# Robot_Board_v003.net
KiCad netlist of a schematic drawn in EAGLE
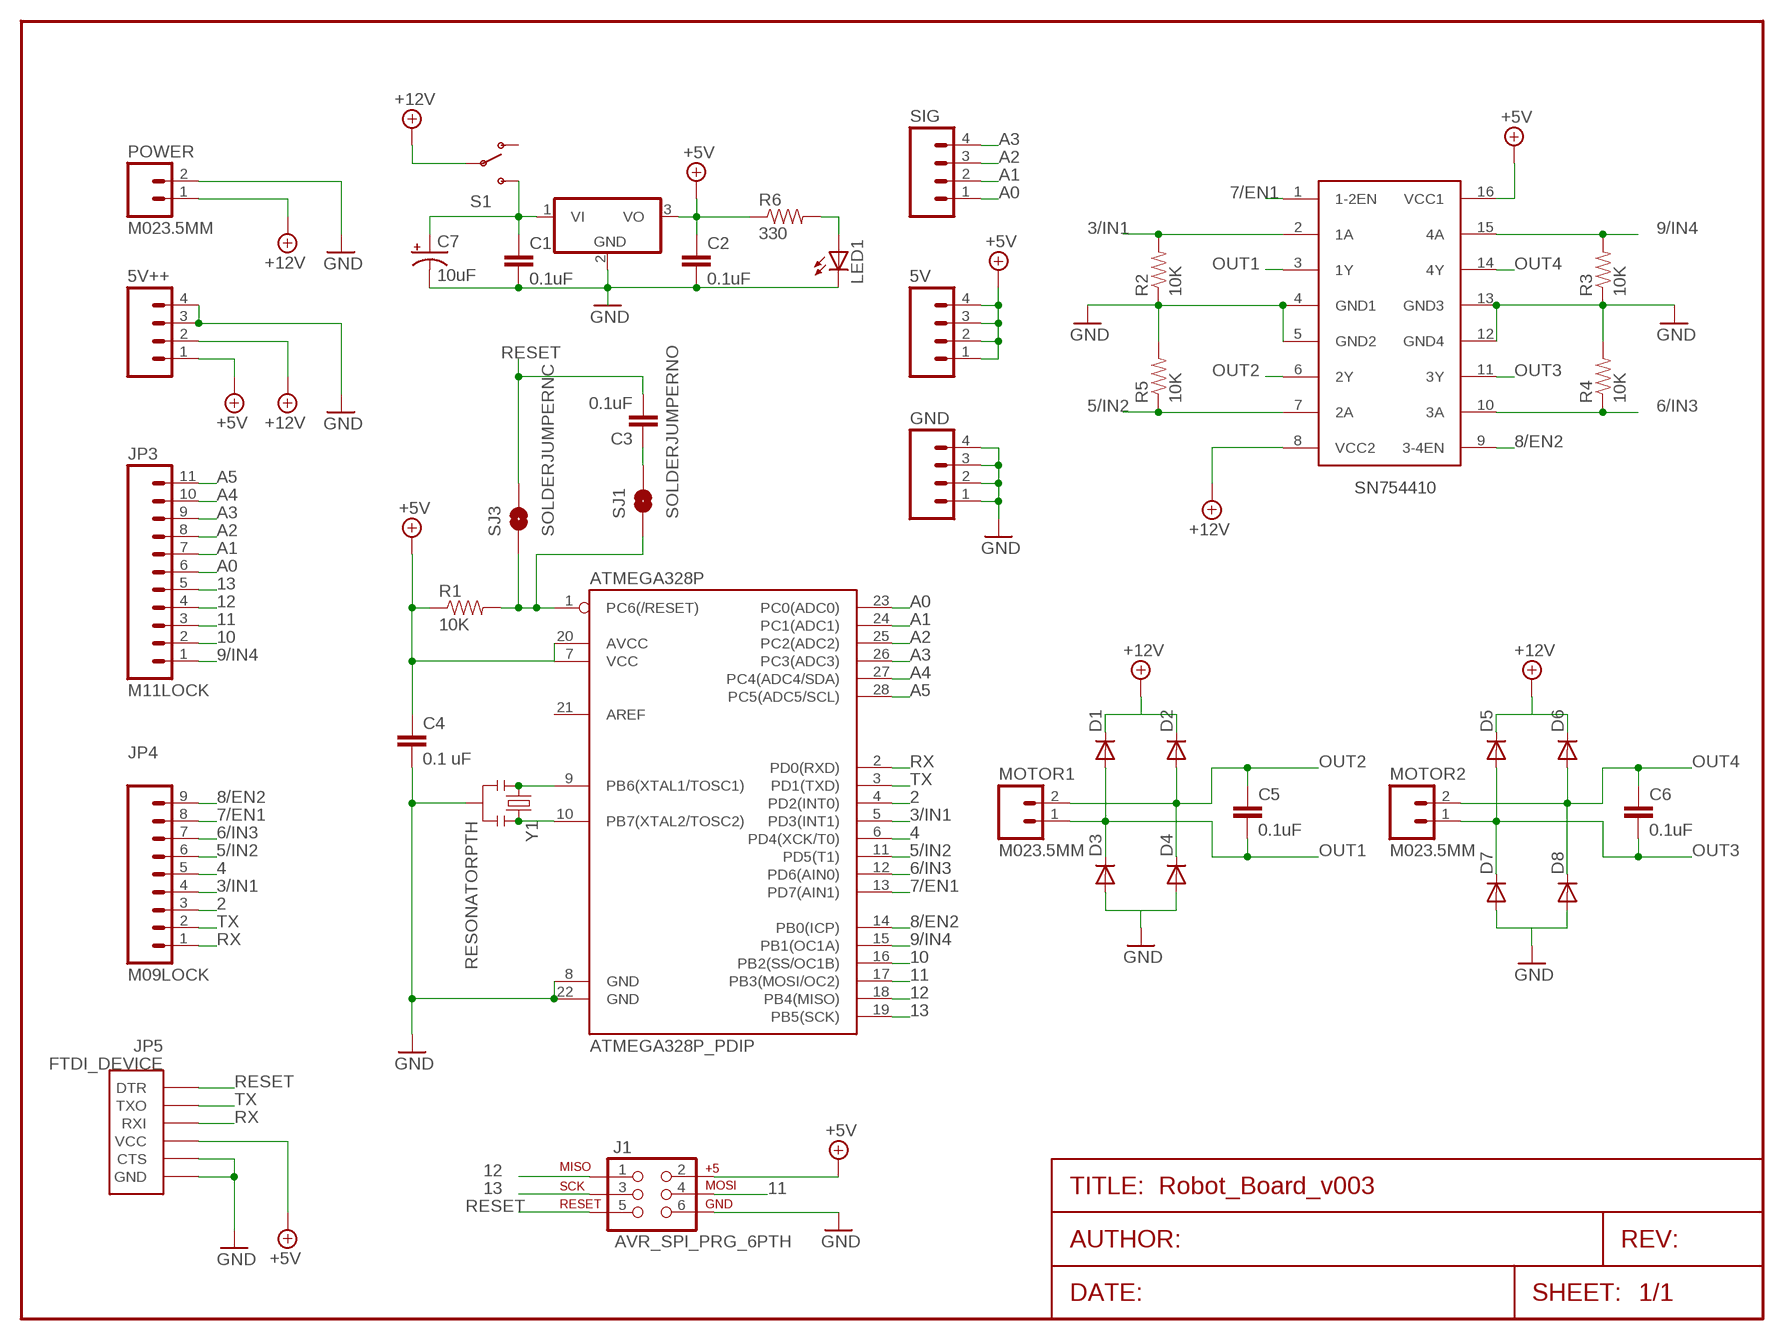
[diagram p0: schematic, sheet 1]

(export (version "E")
  (design (tool "Eeschema 10.0.6"))
  (components
    (comp (ref "5V")
      (value "M04PTH")
      (footprint "eagle-import:1X04")
      (libsource (lib "eagle-import") (part "M04PTH"))
    )
    (comp (ref "5V++")
      (value "M04LOCK")
      (footprint "eagle-import:1X04_LOCK")
      (libsource (lib "eagle-import") (part "M04LOCK"))
    )
    (comp (ref "7805")
      (value "7805TV")
      (footprint "eagle-import:TO220V")
      (libsource (lib "eagle-import") (part "78TV05"))
    )
    (comp (ref "ATMEGA328P")
      (value "ATMEGA328P_PDIP")
      (footprint "eagle-import:DIL28-3")
      (libsource (lib "eagle-import") (part "ATMEGA328P_PDIP"))
    )
    (comp (ref "C1")
      (value "0.1uF")
      (footprint "eagle-import:CAP-PTH-5MM")
      (libsource (lib "eagle-import") (part "CAPPTH1"))
    )
    (comp (ref "C2")
      (value "0.1uF")
      (footprint "eagle-import:CAP-PTH-5MM")
      (libsource (lib "eagle-import") (part "CAPPTH1"))
    )
    (comp (ref "C3")
      (value "0.1uF")
      (footprint "eagle-import:CAP-PTH-5MM")
      (libsource (lib "eagle-import") (part "CAPPTH1"))
    )
    (comp (ref "C4")
      (value "0.1 uF")
      (footprint "eagle-import:CAP-PTH-5MM")
      (libsource (lib "eagle-import") (part "CAPPTH1"))
    )
    (comp (ref "C5")
      (value "0.1uF")
      (footprint "eagle-import:CAP-PTH-5MM")
      (libsource (lib "eagle-import") (part "CAPPTH1"))
    )
    (comp (ref "C6")
      (value "0.1uF")
      (footprint "eagle-import:CAP-PTH-5MM")
      (libsource (lib "eagle-import") (part "CAPPTH1"))
    )
    (comp (ref "C7")
      (value "10uF")
      (footprint "eagle-import:CPOL-RADIAL-10UF-25V")
      (libsource (lib "eagle-import") (part "CAP_POLPTH2"))
    )
    (comp (ref "D1")
      (value "DIODEPTH")
      (footprint "eagle-import:DIODE-1N4001")
      (libsource (lib "eagle-import") (part "DIODEPTH"))
    )
    (comp (ref "D2")
      (value "DIODEPTH")
      (footprint "eagle-import:DIODE-1N4001")
      (libsource (lib "eagle-import") (part "DIODEPTH"))
    )
    (comp (ref "D3")
      (value "DIODEPTH")
      (footprint "eagle-import:DIODE-1N4001")
      (libsource (lib "eagle-import") (part "DIODEPTH"))
    )
    (comp (ref "D4")
      (value "DIODEPTH")
      (footprint "eagle-import:DIODE-1N4001")
      (libsource (lib "eagle-import") (part "DIODEPTH"))
    )
    (comp (ref "D5")
      (value "DIODEPTH")
      (footprint "eagle-import:DIODE-1N4001")
      (libsource (lib "eagle-import") (part "DIODEPTH"))
    )
    (comp (ref "D6")
      (value "DIODEPTH")
      (footprint "eagle-import:DIODE-1N4001")
      (libsource (lib "eagle-import") (part "DIODEPTH"))
    )
    (comp (ref "D7")
      (value "DIODEPTH")
      (footprint "eagle-import:DIODE-1N4001")
      (libsource (lib "eagle-import") (part "DIODEPTH"))
    )
    (comp (ref "D8")
      (value "DIODEPTH")
      (footprint "eagle-import:DIODE-1N4001")
      (libsource (lib "eagle-import") (part "DIODEPTH"))
    )
    (comp (ref "GND")
      (value "M04PTH")
      (footprint "eagle-import:1X04")
      (libsource (lib "eagle-import") (part "M04PTH"))
    )
    (comp (ref "J1")
      (value "AVR_SPI_PRG_6PTH")
      (footprint "eagle-import:2X3")
      (libsource (lib "eagle-import") (part "AVR_SPI_PRG_6PTH"))
    )
    (comp (ref "JP3")
      (value "M11LOCK")
      (footprint "eagle-import:1X11_LOCK")
      (libsource (lib "eagle-import") (part "M11LOCK"))
    )
    (comp (ref "JP4")
      (value "M09LOCK")
      (footprint "eagle-import:1X09_LOCK")
      (libsource (lib "eagle-import") (part "M09LOCK"))
    )
    (comp (ref "JP5")
      (value "FTDI_DEVICE")
      (footprint "eagle-import:FTDI_DEVICE_SIDE")
      (libsource (lib "eagle-import") (part "FTDI_DEVICE"))
    )
    (comp (ref "LED1")
      (value "LED3MM")
      (footprint "eagle-import:LED3MM")
      (libsource (lib "eagle-import") (part "LED3MM"))
    )
    (comp (ref "MOTOR1")
      (value "M023.5MM")
      (footprint "eagle-import:SCREWTERMINAL-3.5MM-2")
      (libsource (lib "eagle-import") (part "M023.5MM"))
    )
    (comp (ref "MOTOR2")
      (value "M023.5MM")
      (footprint "eagle-import:SCREWTERMINAL-3.5MM-2")
      (libsource (lib "eagle-import") (part "M023.5MM"))
    )
    (comp (ref "POWER")
      (value "M023.5MM")
      (footprint "eagle-import:SCREWTERMINAL-3.5MM-2")
      (libsource (lib "eagle-import") (part "M023.5MM"))
    )
    (comp (ref "R1")
      (value "10K")
      (footprint "eagle-import:AXIAL-0.4")
      (libsource (lib "eagle-import") (part "RESISTORPTH-1/4W"))
    )
    (comp (ref "R2")
      (value "10K")
      (footprint "eagle-import:AXIAL-0.4")
      (libsource (lib "eagle-import") (part "RESISTORPTH-1/4W"))
    )
    (comp (ref "R3")
      (value "10K")
      (footprint "eagle-import:AXIAL-0.4")
      (libsource (lib "eagle-import") (part "RESISTORPTH-1/4W"))
    )
    (comp (ref "R4")
      (value "10K")
      (footprint "eagle-import:AXIAL-0.4")
      (libsource (lib "eagle-import") (part "RESISTORPTH-1/4W"))
    )
    (comp (ref "R5")
      (value "10K")
      (footprint "eagle-import:AXIAL-0.4")
      (libsource (lib "eagle-import") (part "RESISTORPTH-1/4W"))
    )
    (comp (ref "R6")
      (value "330")
      (footprint "eagle-import:AXIAL-0.4")
      (libsource (lib "eagle-import") (part "RESISTORPTH-1/4W"))
    )
    (comp (ref "S1")
      (value "SWITCH-SPDTPTH")
      (footprint "eagle-import:SWITCH-SPDT")
      (libsource (lib "eagle-import") (part "SWITCH-SPDTPTH"))
    )
    (comp (ref "SIG")
      (value "M04PTH")
      (footprint "eagle-import:1X04")
      (libsource (lib "eagle-import") (part "M04PTH"))
    )
    (comp (ref "SJ1")
      (value "SOLDERJUMPERNO")
      (footprint "eagle-import:SJ_2S-NO")
      (libsource (lib "eagle-import") (part "SOLDERJUMPERNO"))
    )
    (comp (ref "SJ3")
      (value "SOLDERJUMPERNC")
      (footprint "eagle-import:SJ_2S")
      (libsource (lib "eagle-import") (part "SOLDERJUMPERNC"))
    )
    (comp (ref "SN754410")
      (value "L293D")
      (footprint "eagle-import:DIL16")
      (libsource (lib "eagle-import") (part "L293D"))
    )
    (comp (ref "Y1")
      (value "RESONATORPTH")
      (footprint "eagle-import:RESONATOR-PTH")
      (libsource (lib "eagle-import") (part "RESONATORPTH"))
    )
  )
  (nets
    (net (code "1") (name "+5V") (class "Default")
      (node (ref "5V") (pin "1") (pinfunction "1_1") (pintype "passive"))
      (node (ref "5V") (pin "2") (pinfunction "2_2") (pintype "passive"))
      (node (ref "5V") (pin "3") (pinfunction "3_3") (pintype "passive"))
      (node (ref "5V") (pin "4") (pinfunction "4_4") (pintype "passive"))
      (node (ref "5V++") (pin "1") (pinfunction "1_1") (pintype "passive"))
      (node (ref "7805") (pin "3") (pinfunction "VO_3") (pintype "passive"))
      (node (ref "ATMEGA328P") (pin "20") (pinfunction "AVCC_20") (pintype "bidirectional"))
      (node (ref "ATMEGA328P") (pin "7") (pinfunction "VCC_7") (pintype "bidirectional"))
      (node (ref "C2") (pin "1") (pinfunction "1_1") (pintype "passive"))
      (node (ref "C4") (pin "1") (pinfunction "1_1") (pintype "passive"))
      (node (ref "J1") (pin "2") (pinfunction "2_2") (pintype "passive"))
      (node (ref "JP5") (pin "P$4") (pinfunction "VCC_P$4") (pintype "bidirectional"))
      (node (ref "R1") (pin "P$1") (pinfunction "1_P$1") (pintype "passive"))
      (node (ref "R6") (pin "P$1") (pinfunction "1_P$1") (pintype "passive"))
      (node (ref "SN754410") (pin "16") (pinfunction "VCC1_16") (pintype "power_in"))
    )
    (net (code "2") (name "+12V") (class "Default")
      (node (ref "5V++") (pin "2") (pinfunction "2_2") (pintype "passive"))
      (node (ref "D1") (pin "C") (pinfunction "C_C") (pintype "passive"))
      (node (ref "D2") (pin "C") (pinfunction "C_C") (pintype "passive"))
      (node (ref "D5") (pin "C") (pinfunction "C_C") (pintype "passive"))
      (node (ref "D6") (pin "C") (pinfunction "C_C") (pintype "passive"))
      (node (ref "POWER") (pin "1") (pinfunction "1_1") (pintype "passive"))
      (node (ref "S1") (pin "2") (pinfunction "P_2") (pintype "passive"))
      (node (ref "SN754410") (pin "8") (pinfunction "VCC2_8") (pintype "power_in"))
    )
    (net (code "3") (name "/2") (class "Default")
      (node (ref "ATMEGA328P") (pin "4") (pinfunction "PD2(INT0)_4") (pintype "bidirectional"))
      (node (ref "JP4") (pin "3") (pinfunction "3_3") (pintype "passive"))
    )
    (net (code "4") (name "/3{slash}IN1") (class "Default")
      (node (ref "ATMEGA328P") (pin "5") (pinfunction "PD3(INT1)_5") (pintype "bidirectional"))
      (node (ref "JP4") (pin "4") (pinfunction "4_4") (pintype "passive"))
      (node (ref "R2") (pin "P$2") (pinfunction "2_P$2") (pintype "passive"))
      (node (ref "SN754410") (pin "2") (pinfunction "1A_2") (pintype "input"))
    )
    (net (code "5") (name "/4") (class "Default")
      (node (ref "ATMEGA328P") (pin "6") (pinfunction "PD4(XCK/T0)_6") (pintype "bidirectional"))
      (node (ref "JP4") (pin "5") (pinfunction "5_5") (pintype "passive"))
    )
    (net (code "6") (name "/5{slash}IN2") (class "Default")
      (node (ref "ATMEGA328P") (pin "11") (pinfunction "PD5(T1)_11") (pintype "bidirectional"))
      (node (ref "JP4") (pin "6") (pinfunction "6_6") (pintype "passive"))
      (node (ref "R5") (pin "P$1") (pinfunction "1_P$1") (pintype "passive"))
      (node (ref "SN754410") (pin "7") (pinfunction "2A_7") (pintype "input"))
    )
    (net (code "7") (name "/6{slash}IN3") (class "Default")
      (node (ref "ATMEGA328P") (pin "12") (pinfunction "PD6(AIN0)_12") (pintype "bidirectional"))
      (node (ref "JP4") (pin "7") (pinfunction "7_7") (pintype "passive"))
      (node (ref "R4") (pin "P$1") (pinfunction "1_P$1") (pintype "passive"))
      (node (ref "SN754410") (pin "10") (pinfunction "3A_10") (pintype "input"))
    )
    (net (code "8") (name "/7{slash}EN1") (class "Default")
      (node (ref "ATMEGA328P") (pin "13") (pinfunction "PD7(AIN1)_13") (pintype "bidirectional"))
      (node (ref "JP4") (pin "8") (pinfunction "8_8") (pintype "passive"))
      (node (ref "SN754410") (pin "1") (pinfunction "1-2EN_1") (pintype "input"))
    )
    (net (code "9") (name "/8{slash}EN2") (class "Default")
      (node (ref "ATMEGA328P") (pin "14") (pinfunction "PB0(ICP)_14") (pintype "bidirectional"))
      (node (ref "JP4") (pin "9") (pinfunction "9_9") (pintype "passive"))
      (node (ref "SN754410") (pin "9") (pinfunction "3-4EN_9") (pintype "input"))
    )
    (net (code "10") (name "/9{slash}IN4") (class "Default")
      (node (ref "ATMEGA328P") (pin "15") (pinfunction "PB1(OC1A)_15") (pintype "bidirectional"))
      (node (ref "JP3") (pin "1") (pinfunction "1_1") (pintype "passive"))
      (node (ref "R3") (pin "P$2") (pinfunction "2_P$2") (pintype "passive"))
      (node (ref "SN754410") (pin "15") (pinfunction "4A_15") (pintype "input"))
    )
    (net (code "11") (name "/10") (class "Default")
      (node (ref "ATMEGA328P") (pin "16") (pinfunction "PB2(SS/OC1B)_16") (pintype "bidirectional"))
      (node (ref "JP3") (pin "2") (pinfunction "2_2") (pintype "passive"))
    )
    (net (code "12") (name "/11") (class "Default")
      (node (ref "ATMEGA328P") (pin "17") (pinfunction "PB3(MOSI/OC2)_17") (pintype "bidirectional"))
      (node (ref "J1") (pin "4") (pinfunction "4_4") (pintype "passive"))
      (node (ref "JP3") (pin "3") (pinfunction "3_3") (pintype "passive"))
    )
    (net (code "13") (name "/12") (class "Default")
      (node (ref "ATMEGA328P") (pin "18") (pinfunction "PB4(MISO)_18") (pintype "bidirectional"))
      (node (ref "J1") (pin "1") (pinfunction "1_1") (pintype "passive"))
      (node (ref "JP3") (pin "4") (pinfunction "4_4") (pintype "passive"))
    )
    (net (code "14") (name "/13") (class "Default")
      (node (ref "ATMEGA328P") (pin "19") (pinfunction "PB5(SCK)_19") (pintype "bidirectional"))
      (node (ref "J1") (pin "3") (pinfunction "3_3") (pintype "passive"))
      (node (ref "JP3") (pin "5") (pinfunction "5_5") (pintype "passive"))
    )
    (net (code "15") (name "/A0") (class "Default")
      (node (ref "ATMEGA328P") (pin "23") (pinfunction "PC0(ADC0)_23") (pintype "bidirectional"))
      (node (ref "JP3") (pin "6") (pinfunction "6_6") (pintype "passive"))
      (node (ref "SIG") (pin "1") (pinfunction "1_1") (pintype "passive"))
    )
    (net (code "16") (name "/A1") (class "Default")
      (node (ref "ATMEGA328P") (pin "24") (pinfunction "PC1(ADC1)_24") (pintype "bidirectional"))
      (node (ref "JP3") (pin "7") (pinfunction "7_7") (pintype "passive"))
      (node (ref "SIG") (pin "2") (pinfunction "2_2") (pintype "passive"))
    )
    (net (code "17") (name "/A2") (class "Default")
      (node (ref "ATMEGA328P") (pin "25") (pinfunction "PC2(ADC2)_25") (pintype "bidirectional"))
      (node (ref "JP3") (pin "8") (pinfunction "8_8") (pintype "passive"))
      (node (ref "SIG") (pin "3") (pinfunction "3_3") (pintype "passive"))
    )
    (net (code "18") (name "/A3") (class "Default")
      (node (ref "ATMEGA328P") (pin "26") (pinfunction "PC3(ADC3)_26") (pintype "bidirectional"))
      (node (ref "JP3") (pin "9") (pinfunction "9_9") (pintype "passive"))
      (node (ref "SIG") (pin "4") (pinfunction "4_4") (pintype "passive"))
    )
    (net (code "19") (name "/A4") (class "Default")
      (node (ref "ATMEGA328P") (pin "27") (pinfunction "PC4(ADC4/SDA)_27") (pintype "bidirectional"))
      (node (ref "JP3") (pin "10") (pinfunction "10_10") (pintype "passive"))
    )
    (net (code "20") (name "/A5") (class "Default")
      (node (ref "ATMEGA328P") (pin "28") (pinfunction "PC5(ADC5/SCL)_28") (pintype "bidirectional"))
      (node (ref "JP3") (pin "11") (pinfunction "11_11") (pintype "passive"))
    )
    (net (code "21") (name "/OUT1") (class "Default")
      (node (ref "C5") (pin "2") (pinfunction "2_2") (pintype "passive"))
      (node (ref "D1") (pin "A") (pinfunction "A_A") (pintype "passive"))
      (node (ref "D3") (pin "C") (pinfunction "C_C") (pintype "passive"))
      (node (ref "MOTOR1") (pin "1") (pinfunction "1_1") (pintype "passive"))
      (node (ref "SN754410") (pin "3") (pinfunction "1Y_3") (pintype "output"))
    )
    (net (code "22") (name "/OUT2") (class "Default")
      (node (ref "C5") (pin "1") (pinfunction "1_1") (pintype "passive"))
      (node (ref "D2") (pin "A") (pinfunction "A_A") (pintype "passive"))
      (node (ref "D4") (pin "C") (pinfunction "C_C") (pintype "passive"))
      (node (ref "MOTOR1") (pin "2") (pinfunction "2_2") (pintype "passive"))
      (node (ref "SN754410") (pin "6") (pinfunction "2Y_6") (pintype "output"))
    )
    (net (code "23") (name "/OUT3") (class "Default")
      (node (ref "C6") (pin "2") (pinfunction "2_2") (pintype "passive"))
      (node (ref "D5") (pin "A") (pinfunction "A_A") (pintype "passive"))
      (node (ref "D7") (pin "C") (pinfunction "C_C") (pintype "passive"))
      (node (ref "MOTOR2") (pin "1") (pinfunction "1_1") (pintype "passive"))
      (node (ref "SN754410") (pin "11") (pinfunction "3Y_11") (pintype "output"))
    )
    (net (code "24") (name "/OUT4") (class "Default")
      (node (ref "C6") (pin "1") (pinfunction "1_1") (pintype "passive"))
      (node (ref "D6") (pin "A") (pinfunction "A_A") (pintype "passive"))
      (node (ref "D8") (pin "C") (pinfunction "C_C") (pintype "passive"))
      (node (ref "MOTOR2") (pin "2") (pinfunction "2_2") (pintype "passive"))
      (node (ref "SN754410") (pin "14") (pinfunction "4Y_14") (pintype "output"))
    )
    (net (code "25") (name "/RESET") (class "Default")
      (node (ref "C3") (pin "2") (pinfunction "2_2") (pintype "passive"))
      (node (ref "J1") (pin "5") (pinfunction "5_5") (pintype "passive"))
      (node (ref "JP5") (pin "P$1") (pinfunction "DTR_P$1") (pintype "bidirectional"))
      (node (ref "SJ3") (pin "2") (pinfunction "2_2") (pintype "passive"))
    )
    (net (code "26") (name "/RX") (class "Default")
      (node (ref "ATMEGA328P") (pin "2") (pinfunction "PD0(RXD)_2") (pintype "bidirectional"))
      (node (ref "JP4") (pin "1") (pinfunction "1_1") (pintype "passive"))
      (node (ref "JP5") (pin "P$3") (pinfunction "RXI_P$3") (pintype "bidirectional"))
    )
    (net (code "27") (name "/TX") (class "Default")
      (node (ref "ATMEGA328P") (pin "3") (pinfunction "PD1(TXD)_3") (pintype "bidirectional"))
      (node (ref "JP4") (pin "2") (pinfunction "2_2") (pintype "passive"))
      (node (ref "JP5") (pin "P$2") (pinfunction "TXO_P$2") (pintype "bidirectional"))
    )
    (net (code "28") (name "GND") (class "Default")
      (node (ref "5V++") (pin "3") (pinfunction "3_3") (pintype "passive"))
      (node (ref "5V++") (pin "4") (pinfunction "4_4") (pintype "passive"))
      (node (ref "7805") (pin "2") (pinfunction "GND_2") (pintype "passive"))
      (node (ref "ATMEGA328P") (pin "22") (pinfunction "GND_22") (pintype "bidirectional"))
      (node (ref "ATMEGA328P") (pin "8") (pinfunction "GND_8") (pintype "bidirectional"))
      (node (ref "C1") (pin "2") (pinfunction "2_2") (pintype "passive"))
      (node (ref "C2") (pin "2") (pinfunction "2_2") (pintype "passive"))
      (node (ref "C4") (pin "2") (pinfunction "2_2") (pintype "passive"))
      (node (ref "C7") (pin "2") (pinfunction "-_2") (pintype "passive"))
      (node (ref "D3") (pin "A") (pinfunction "A_A") (pintype "passive"))
      (node (ref "D4") (pin "A") (pinfunction "A_A") (pintype "passive"))
      (node (ref "D7") (pin "A") (pinfunction "A_A") (pintype "passive"))
      (node (ref "D8") (pin "A") (pinfunction "A_A") (pintype "passive"))
      (node (ref "GND") (pin "1") (pinfunction "1_1") (pintype "passive"))
      (node (ref "GND") (pin "2") (pinfunction "2_2") (pintype "passive"))
      (node (ref "GND") (pin "3") (pinfunction "3_3") (pintype "passive"))
      (node (ref "GND") (pin "4") (pinfunction "4_4") (pintype "passive"))
      (node (ref "J1") (pin "6") (pinfunction "6_6") (pintype "passive"))
      (node (ref "JP5") (pin "P$5") (pinfunction "CTS_P$5") (pintype "bidirectional"))
      (node (ref "JP5") (pin "P$6") (pinfunction "GND_P$6") (pintype "bidirectional"))
      (node (ref "LED1") (pin "K") (pinfunction "C_K") (pintype "passive"))
      (node (ref "POWER") (pin "2") (pinfunction "2_2") (pintype "passive"))
      (node (ref "R2") (pin "P$1") (pinfunction "1_P$1") (pintype "passive"))
      (node (ref "R3") (pin "P$1") (pinfunction "1_P$1") (pintype "passive"))
      (node (ref "R4") (pin "P$2") (pinfunction "2_P$2") (pintype "passive"))
      (node (ref "R5") (pin "P$2") (pinfunction "2_P$2") (pintype "passive"))
      (node (ref "SN754410") (pin "12") (pinfunction "GND4_12") (pintype "power_in"))
      (node (ref "SN754410") (pin "13") (pinfunction "GND3_13") (pintype "power_in"))
      (node (ref "SN754410") (pin "4") (pinfunction "GND1_4") (pintype "power_in"))
      (node (ref "SN754410") (pin "5") (pinfunction "GND2_5") (pintype "power_in"))
      (node (ref "Y1") (pin "2") (pinfunction "2_2") (pintype "passive"))
    )
    (net (code "29") (name "Net-(7805-VI)") (class "Default")
      (node (ref "7805") (pin "1") (pinfunction "VI_1") (pintype "input"))
      (node (ref "C1") (pin "1") (pinfunction "1_1") (pintype "passive"))
      (node (ref "C7") (pin "1") (pinfunction "+_1") (pintype "passive"))
      (node (ref "S1") (pin "3") (pinfunction "S_3") (pintype "passive"))
    )
    (net (code "30") (name "Net-(ATMEGA328P-PB6(XTAL1{slash}TOSC1))") (class "Default")
      (node (ref "ATMEGA328P") (pin "9") (pinfunction "PB6(XTAL1/TOSC1)_9") (pintype "bidirectional"))
      (node (ref "Y1") (pin "1") (pinfunction "1_1") (pintype "passive"))
    )
    (net (code "31") (name "Net-(ATMEGA328P-PB7(XTAL2{slash}TOSC2))") (class "Default")
      (node (ref "ATMEGA328P") (pin "10") (pinfunction "PB7(XTAL2/TOSC2)_10") (pintype "bidirectional"))
      (node (ref "Y1") (pin "3") (pinfunction "3_3") (pintype "passive"))
    )
    (net (code "32") (name "Net-(ATMEGA328P-PC6({slash}RESET))") (class "Default")
      (node (ref "ATMEGA328P") (pin "1") (pinfunction "PC6(/RESET)_1") (pintype "bidirectional"))
      (node (ref "R1") (pin "P$2") (pinfunction "2_P$2") (pintype "passive"))
      (node (ref "SJ1") (pin "1") (pinfunction "1_1") (pintype "passive"))
      (node (ref "SJ3") (pin "1") (pinfunction "1_1") (pintype "passive"))
    )
    (net (code "33") (name "Net-(C3-Pad1)") (class "Default")
      (node (ref "C3") (pin "1") (pinfunction "1_1") (pintype "passive"))
      (node (ref "SJ1") (pin "2") (pinfunction "2_2") (pintype "passive"))
    )
    (net (code "34") (name "Net-(R6-2)") (class "Default")
      (node (ref "LED1") (pin "A") (pinfunction "A_A") (pintype "passive"))
      (node (ref "R6") (pin "P$2") (pinfunction "2_P$2") (pintype "passive"))
    )
    (net (code "35") (name "unconnected-(ATMEGA328P-AREF-Pad21)") (class "Default")
      (node (ref "ATMEGA328P") (pin "21") (pinfunction "AREF_21") (pintype "bidirectional"))
    )
    (net (code "36") (name "unconnected-(S1-O-Pad1)") (class "Default")
      (node (ref "S1") (pin "1") (pinfunction "O_1") (pintype "passive"))
    )
  )
)
